# base_module_e1.net
KiCad netlist of a schematic drawn in EAGLE
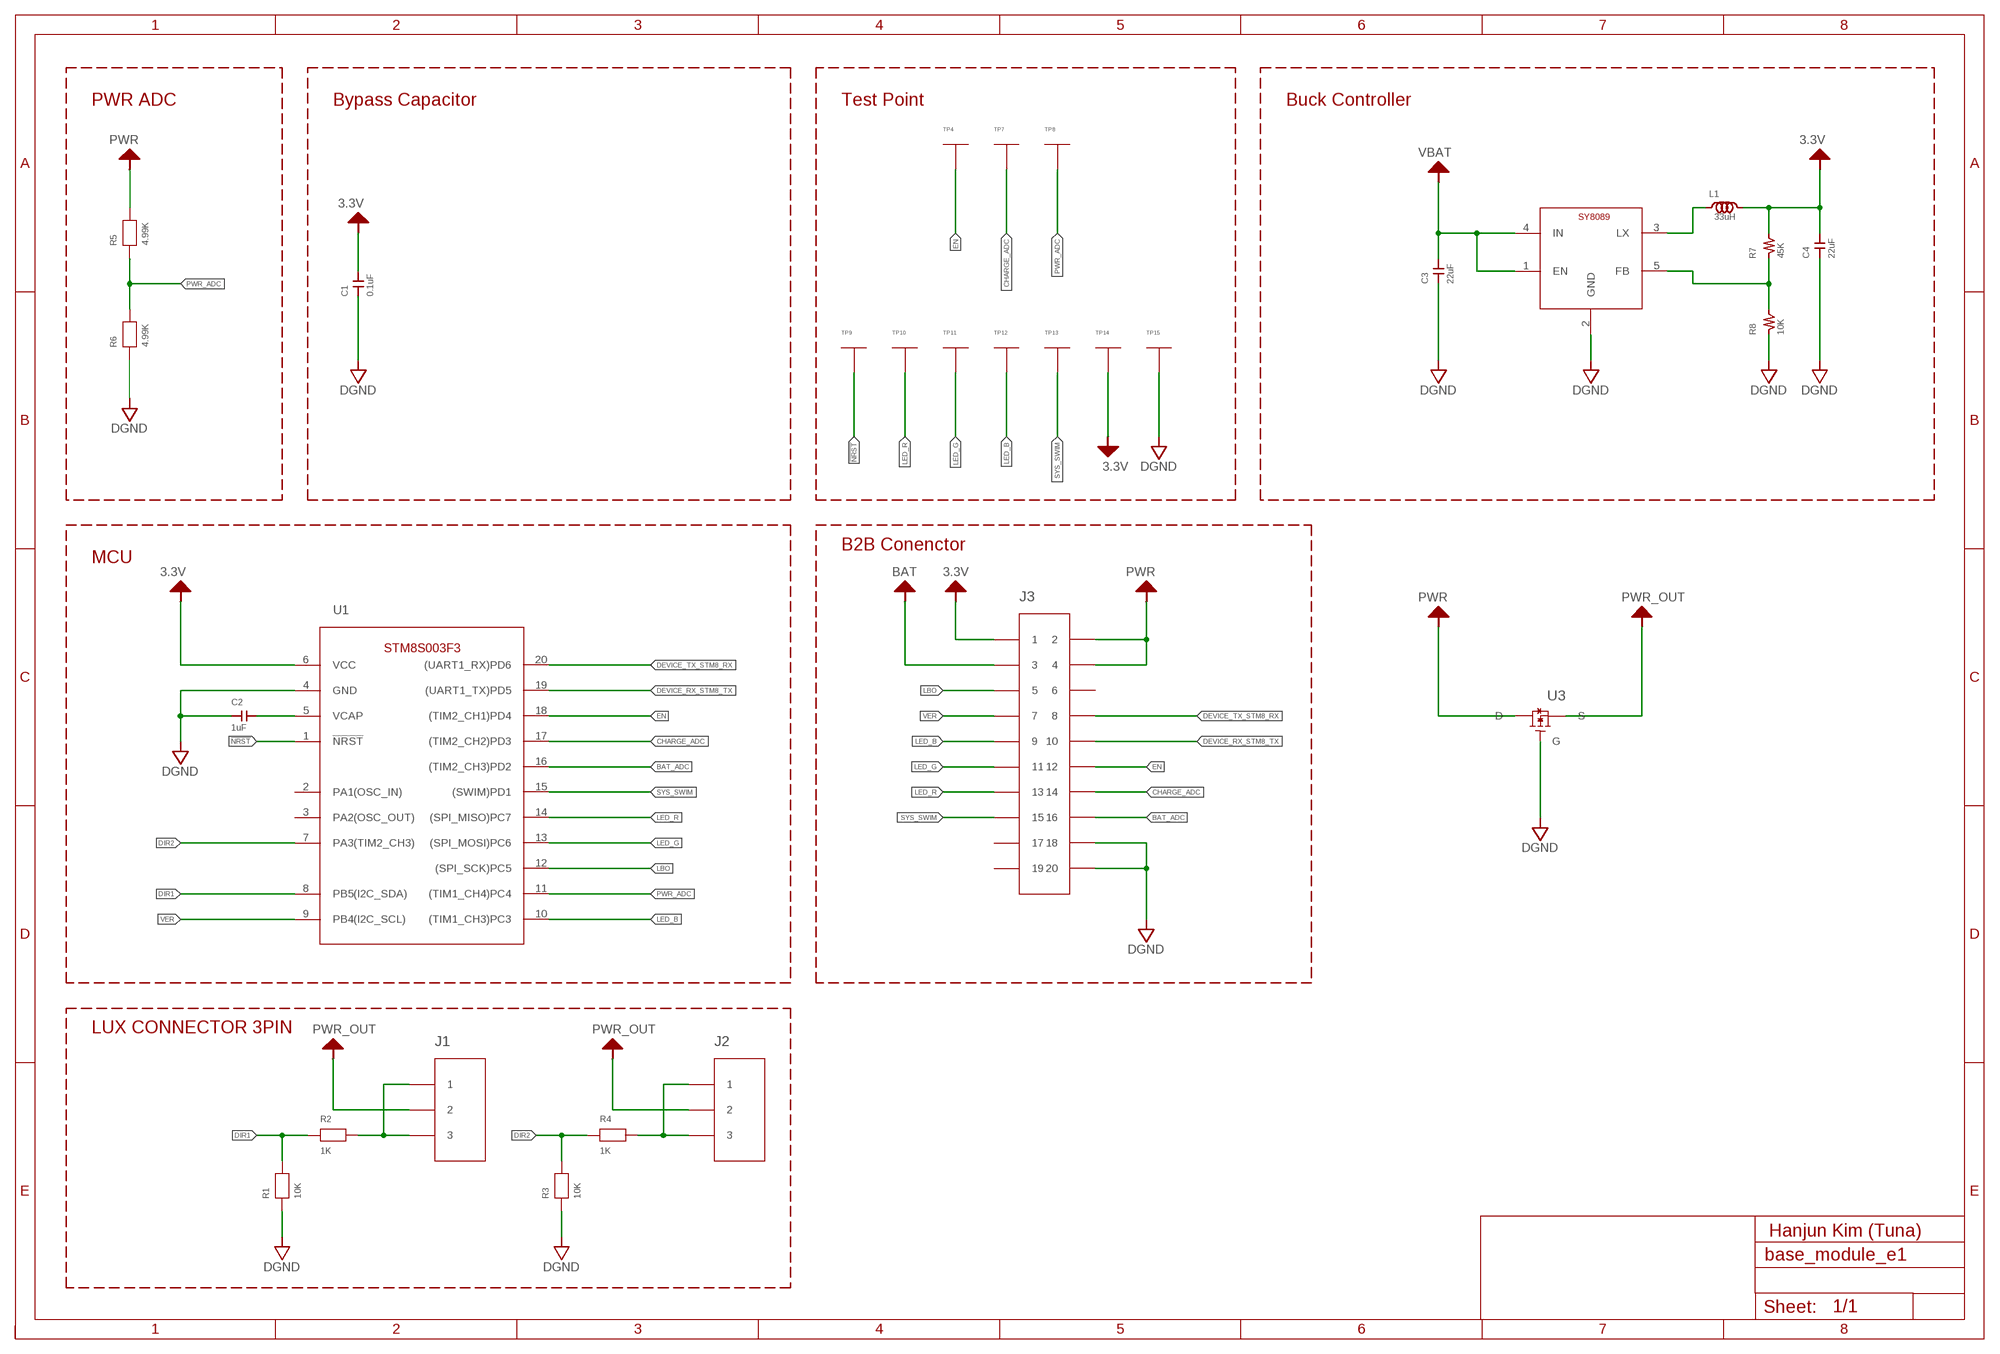
[diagram p0: schematic, sheet 1]

(export (version "E")
  (design (tool "Eeschema 10.0.6"))
  (components
    (comp (ref "C1")
      (value "0.1uF")
      (footprint "eagle-import:1005")
      (libsource (lib "eagle-import") (part "CAPACITOR_CHIP1005"))
    )
    (comp (ref "C2")
      (value "1uF")
      (footprint "eagle-import:1005")
      (libsource (lib "eagle-import") (part "CAPACITOR_CHIP1005"))
    )
    (comp (ref "C3")
      (value "22uF")
      (footprint "eagle-import:1608")
      (libsource (lib "eagle-import") (part "CAPACITOR_CHIP1608"))
    )
    (comp (ref "C4")
      (value "22uF")
      (footprint "eagle-import:1608")
      (libsource (lib "eagle-import") (part "CAPACITOR_CHIP1608"))
    )
    (comp (ref "J1")
      (value "MODI_CONNECTOR_BOTTOM")
      (footprint "eagle-import:3P")
      (libsource (lib "eagle-import") (part "MODI_CONNECTOR_BOTTOM"))
    )
    (comp (ref "J2")
      (value "MODI_CONNECTOR_BOTTOM")
      (footprint "eagle-import:3P")
      (libsource (lib "eagle-import") (part "MODI_CONNECTOR_BOTTOM"))
    )
    (comp (ref "J3")
      (value "AXK720447G")
      (footprint "eagle-import:SOCKET_20P")
      (libsource (lib "eagle-import") (part "AXK720447G"))
    )
    (comp (ref "L1")
      (value "33uH")
      (footprint "eagle-import:2518")
      (libsource (lib "eagle-import") (part "INDUCTOR2518"))
    )
    (comp (ref "P1")
      (value "MODI_BAT_BASE")
      (footprint "eagle-import:BAT_BASE")
      (libsource (lib "eagle-import") (part "MODI_BAT_BASE"))
    )
    (comp (ref "R1")
      (value "10K")
      (footprint "eagle-import:1005")
      (libsource (lib "eagle-import") (part "RESISTOR_CHIP_SMALL1005"))
    )
    (comp (ref "R2")
      (value "1K")
      (footprint "eagle-import:1005")
      (libsource (lib "eagle-import") (part "RESISTOR_CHIP_SMALL1005"))
    )
    (comp (ref "R3")
      (value "10K")
      (footprint "eagle-import:1005")
      (libsource (lib "eagle-import") (part "RESISTOR_CHIP_SMALL1005"))
    )
    (comp (ref "R4")
      (value "1K")
      (footprint "eagle-import:1005")
      (libsource (lib "eagle-import") (part "RESISTOR_CHIP_SMALL1005"))
    )
    (comp (ref "R5")
      (value "4.99K")
      (footprint "eagle-import:1005")
      (libsource (lib "eagle-import") (part "RESISTOR_CHIP_SMALL1005"))
    )
    (comp (ref "R6")
      (value "4.99K")
      (footprint "eagle-import:1005")
      (libsource (lib "eagle-import") (part "RESISTOR_CHIP_SMALL1005"))
    )
    (comp (ref "R7")
      (value "45K")
      (footprint "eagle-import:1005")
      (libsource (lib "eagle-import") (part "RESISTOR_CHIP_1005"))
    )
    (comp (ref "R8")
      (value "10K")
      (footprint "eagle-import:1005")
      (libsource (lib "eagle-import") (part "RESISTOR_CHIP_1005"))
    )
    (comp (ref "TP4")
      (value "TEST_POINT_1.2MM_PAD")
      (footprint "eagle-import:1.2MM_PAD")
      (libsource (lib "eagle-import") (part "TEST_POINT_1.2MM_PAD"))
    )
    (comp (ref "TP7")
      (value "TEST_POINT_1.2MM_PAD")
      (footprint "eagle-import:1.2MM_PAD")
      (libsource (lib "eagle-import") (part "TEST_POINT_1.2MM_PAD"))
    )
    (comp (ref "TP8")
      (value "TEST_POINT_1.2MM_PAD")
      (footprint "eagle-import:1.2MM_PAD")
      (libsource (lib "eagle-import") (part "TEST_POINT_1.2MM_PAD"))
    )
    (comp (ref "TP9")
      (value "TEST_POINT_1.2MM_PAD")
      (footprint "eagle-import:1.2MM_PAD")
      (libsource (lib "eagle-import") (part "TEST_POINT_1.2MM_PAD"))
    )
    (comp (ref "TP10")
      (value "TEST_POINT_1.2MM_PAD")
      (footprint "eagle-import:1.2MM_PAD")
      (libsource (lib "eagle-import") (part "TEST_POINT_1.2MM_PAD"))
    )
    (comp (ref "TP11")
      (value "TEST_POINT_1.2MM_PAD")
      (footprint "eagle-import:1.2MM_PAD")
      (libsource (lib "eagle-import") (part "TEST_POINT_1.2MM_PAD"))
    )
    (comp (ref "TP12")
      (value "TEST_POINT_1.2MM_PAD")
      (footprint "eagle-import:1.2MM_PAD")
      (libsource (lib "eagle-import") (part "TEST_POINT_1.2MM_PAD"))
    )
    (comp (ref "TP13")
      (value "TEST_POINT")
      (footprint "eagle-import:0.7MM_HOLE")
      (libsource (lib "eagle-import") (part "TEST_POINT"))
    )
    (comp (ref "TP14")
      (value "TEST_POINT")
      (footprint "eagle-import:0.7MM_HOLE")
      (libsource (lib "eagle-import") (part "TEST_POINT"))
    )
    (comp (ref "TP15")
      (value "TEST_POINT")
      (footprint "eagle-import:0.7MM_HOLE")
      (libsource (lib "eagle-import") (part "TEST_POINT"))
    )
    (comp (ref "U1")
      (value "STM8S003FXU6")
      (footprint "eagle-import:UFQFPN20")
      (libsource (lib "eagle-import") (part "STM8S003FXU6"))
    )
    (comp (ref "U2")
      (value "SY8089")
      (footprint "eagle-import:SOT-23-5")
      (libsource (lib "eagle-import") (part "SY8089"))
    )
    (comp (ref "U3")
      (value "PMXBXXXXPE")
      (footprint "eagle-import:DFN1010D-3")
      (libsource (lib "eagle-import") (part "PMXBXXXXPE"))
    )
  )
  (nets
    (net (code "1") (name "/~{NRST}") (class "Default")
      (node (ref "TP9") (pin "P1") (pinfunction "P$1_P1") (pintype "bidirectional"))
      (node (ref "U1") (pin "1") (pinfunction "~{NRST}_1") (pintype "bidirectional"))
    )
    (net (code "2") (name "3.3V") (class "Default")
      (node (ref "C1") (pin "P$2") (pinfunction "P$2_P$2") (pintype "passive"))
      (node (ref "C4") (pin "P$2") (pinfunction "P$2_P$2") (pintype "passive"))
      (node (ref "J3") (pin "P1") (pinfunction "1_P1") (pintype "bidirectional"))
      (node (ref "L1") (pin "P$2") (pinfunction "P$2_P$2") (pintype "passive"))
      (node (ref "R7") (pin "P$2") (pinfunction "P$2_P$2") (pintype "passive"))
      (node (ref "TP14") (pin "1") (pinfunction "P$1_1") (pintype "bidirectional"))
      (node (ref "U1") (pin "6") (pinfunction "VCC_6") (pintype "power_in"))
    )
    (net (code "3") (name "BAT") (class "Default")
      (node (ref "C3") (pin "P$2") (pinfunction "P$2_P$2") (pintype "passive"))
      (node (ref "J3") (pin "P3") (pinfunction "3_P3") (pintype "bidirectional"))
      (node (ref "U2") (pin "1") (pinfunction "EN_1") (pintype "bidirectional"))
      (node (ref "U2") (pin "4") (pinfunction "IN_4") (pintype "input"))
    )
    (net (code "4") (name "BAT_ADC") (class "Default")
      (node (ref "J3") (pin "P16") (pinfunction "16_P16") (pintype "bidirectional"))
      (node (ref "U1") (pin "16") (pinfunction "(TIM2_CH3)PD2_16") (pintype "bidirectional"))
    )
    (net (code "5") (name "CHARGE_ADC") (class "Default")
      (node (ref "J3") (pin "P14") (pinfunction "14_P14") (pintype "bidirectional"))
      (node (ref "TP7") (pin "P1") (pinfunction "P$1_P1") (pintype "bidirectional"))
      (node (ref "U1") (pin "17") (pinfunction "(TIM2_CH2)PD3_17") (pintype "bidirectional"))
    )
    (net (code "6") (name "DEVICE_RX_STM8_TX") (class "Default")
      (node (ref "J3") (pin "P10") (pinfunction "10_P10") (pintype "bidirectional"))
      (node (ref "U1") (pin "19") (pinfunction "(UART1_TX)PD5_19") (pintype "bidirectional"))
    )
    (net (code "7") (name "DEVICE_TX_STM8_RX") (class "Default")
      (node (ref "J3") (pin "P8") (pinfunction "8_P8") (pintype "bidirectional"))
      (node (ref "U1") (pin "20") (pinfunction "(UART1_RX)PD6_20") (pintype "bidirectional"))
    )
    (net (code "8") (name "DGND") (class "Default")
      (node (ref "C1") (pin "P$1") (pinfunction "P$1_P$1") (pintype "passive"))
      (node (ref "C2") (pin "P$1") (pinfunction "P$1_P$1") (pintype "passive"))
      (node (ref "C3") (pin "P$1") (pinfunction "P$1_P$1") (pintype "passive"))
      (node (ref "C4") (pin "P$1") (pinfunction "P$1_P$1") (pintype "passive"))
      (node (ref "J3") (pin "P18") (pinfunction "18_P18") (pintype "bidirectional"))
      (node (ref "J3") (pin "P20") (pinfunction "20_P20") (pintype "bidirectional"))
      (node (ref "R1") (pin "P$1") (pinfunction "P$1_P$1") (pintype "bidirectional"))
      (node (ref "R3") (pin "P$1") (pinfunction "P$1_P$1") (pintype "bidirectional"))
      (node (ref "R6") (pin "P$1") (pinfunction "P$1_P$1") (pintype "bidirectional"))
      (node (ref "R8") (pin "P$1") (pinfunction "P$1_P$1") (pintype "passive"))
      (node (ref "TP15") (pin "1") (pinfunction "P$1_1") (pintype "bidirectional"))
      (node (ref "U1") (pin "4") (pinfunction "GND_4") (pintype "power_in"))
      (node (ref "U2") (pin "2") (pinfunction "GND_2") (pintype "power_in"))
      (node (ref "U3") (pin "P1") (pinfunction "G_P1") (pintype "bidirectional"))
    )
    (net (code "9") (name "DIR1") (class "Default")
      (node (ref "R1") (pin "P$2") (pinfunction "P$2_P$2") (pintype "bidirectional"))
      (node (ref "R2") (pin "P$1") (pinfunction "P$1_P$1") (pintype "bidirectional"))
      (node (ref "U1") (pin "8") (pinfunction "PB5(I2C_SDA)_8") (pintype "bidirectional"))
    )
    (net (code "10") (name "DIR2") (class "Default")
      (node (ref "R3") (pin "P$2") (pinfunction "P$2_P$2") (pintype "bidirectional"))
      (node (ref "R4") (pin "P$1") (pinfunction "P$1_P$1") (pintype "bidirectional"))
      (node (ref "U1") (pin "7") (pinfunction "PA3(TIM2_CH3)_7") (pintype "bidirectional"))
    )
    (net (code "11") (name "EN") (class "Default")
      (node (ref "J3") (pin "P12") (pinfunction "12_P12") (pintype "bidirectional"))
      (node (ref "TP4") (pin "P1") (pinfunction "P$1_P1") (pintype "bidirectional"))
      (node (ref "U1") (pin "18") (pinfunction "(TIM2_CH1)PD4_18") (pintype "bidirectional"))
    )
    (net (code "12") (name "LBO") (class "Default")
      (node (ref "J3") (pin "P5") (pinfunction "5_P5") (pintype "bidirectional"))
      (node (ref "U1") (pin "12") (pinfunction "(SPI_SCK)PC5_12") (pintype "bidirectional"))
    )
    (net (code "13") (name "LED_B") (class "Default")
      (node (ref "J3") (pin "P9") (pinfunction "9_P9") (pintype "bidirectional"))
      (node (ref "TP12") (pin "P1") (pinfunction "P$1_P1") (pintype "bidirectional"))
      (node (ref "U1") (pin "10") (pinfunction "(TIM1_CH3)PC3_10") (pintype "bidirectional"))
    )
    (net (code "14") (name "LED_G") (class "Default")
      (node (ref "J3") (pin "P11") (pinfunction "11_P11") (pintype "bidirectional"))
      (node (ref "TP11") (pin "P1") (pinfunction "P$1_P1") (pintype "bidirectional"))
      (node (ref "U1") (pin "13") (pinfunction "(SPI_MOSI)PC6_13") (pintype "bidirectional"))
    )
    (net (code "15") (name "LED_R") (class "Default")
      (node (ref "J3") (pin "P13") (pinfunction "13_P13") (pintype "bidirectional"))
      (node (ref "TP10") (pin "P1") (pinfunction "P$1_P1") (pintype "bidirectional"))
      (node (ref "U1") (pin "14") (pinfunction "(SPI_MISO)PC7_14") (pintype "bidirectional"))
    )
    (net (code "16") (name "Net-(J1-1)") (class "Default")
      (node (ref "J1") (pin "P1") (pinfunction "1_P1") (pintype "bidirectional"))
      (node (ref "J1") (pin "P3") (pinfunction "3_P3") (pintype "bidirectional"))
      (node (ref "R2") (pin "P$2") (pinfunction "P$2_P$2") (pintype "bidirectional"))
    )
    (net (code "17") (name "Net-(J2-1)") (class "Default")
      (node (ref "J2") (pin "P1") (pinfunction "1_P1") (pintype "bidirectional"))
      (node (ref "J2") (pin "P3") (pinfunction "3_P3") (pintype "bidirectional"))
      (node (ref "R4") (pin "P$2") (pinfunction "P$2_P$2") (pintype "bidirectional"))
    )
    (net (code "18") (name "Net-(U1-VCAP)") (class "Default")
      (node (ref "C2") (pin "P$2") (pinfunction "P$2_P$2") (pintype "passive"))
      (node (ref "U1") (pin "5") (pinfunction "VCAP_5") (pintype "power_in"))
    )
    (net (code "19") (name "Net-(U2-FB)") (class "Default")
      (node (ref "R7") (pin "P$1") (pinfunction "P$1_P$1") (pintype "passive"))
      (node (ref "R8") (pin "P$2") (pinfunction "P$2_P$2") (pintype "passive"))
      (node (ref "U2") (pin "5") (pinfunction "FB_5") (pintype "power_in"))
    )
    (net (code "20") (name "Net-(U2-LX)") (class "Default")
      (node (ref "L1") (pin "P$1") (pinfunction "P$1_P$1") (pintype "passive"))
      (node (ref "U2") (pin "3") (pinfunction "LX_3") (pintype "bidirectional"))
    )
    (net (code "21") (name "PWR") (class "Default")
      (node (ref "J3") (pin "P2") (pinfunction "2_P2") (pintype "bidirectional"))
      (node (ref "J3") (pin "P4") (pinfunction "4_P4") (pintype "bidirectional"))
      (node (ref "R5") (pin "P$2") (pinfunction "P$2_P$2") (pintype "bidirectional"))
      (node (ref "U3") (pin "P3") (pinfunction "D_P3") (pintype "bidirectional"))
    )
    (net (code "22") (name "PWR_ADC") (class "Default")
      (node (ref "R5") (pin "P$1") (pinfunction "P$1_P$1") (pintype "bidirectional"))
      (node (ref "R6") (pin "P$2") (pinfunction "P$2_P$2") (pintype "bidirectional"))
      (node (ref "TP8") (pin "P1") (pinfunction "P$1_P1") (pintype "bidirectional"))
      (node (ref "U1") (pin "11") (pinfunction "(TIM1_CH4)PC4_11") (pintype "bidirectional"))
    )
    (net (code "23") (name "PWR_OUT") (class "Default")
      (node (ref "J1") (pin "P2") (pinfunction "2_P2") (pintype "bidirectional"))
      (node (ref "J2") (pin "P2") (pinfunction "2_P2") (pintype "bidirectional"))
      (node (ref "U3") (pin "P2") (pinfunction "S_P2") (pintype "bidirectional"))
    )
    (net (code "24") (name "SYS_SWIM") (class "Default")
      (node (ref "J3") (pin "P15") (pinfunction "15_P15") (pintype "bidirectional"))
      (node (ref "TP13") (pin "1") (pinfunction "P$1_1") (pintype "bidirectional"))
      (node (ref "U1") (pin "15") (pinfunction "(SWIM)PD1_15") (pintype "bidirectional"))
    )
    (net (code "25") (name "VER") (class "Default")
      (node (ref "J3") (pin "P7") (pinfunction "7_P7") (pintype "bidirectional"))
      (node (ref "U1") (pin "9") (pinfunction "PB4(I2C_SCL)_9") (pintype "bidirectional"))
    )
    (net (code "26") (name "unconnected-(J3-6-PadP6)") (class "Default")
      (node (ref "J3") (pin "P6") (pinfunction "6_P6") (pintype "bidirectional"))
    )
    (net (code "27") (name "unconnected-(J3-17-PadP17)") (class "Default")
      (node (ref "J3") (pin "P17") (pinfunction "17_P17") (pintype "bidirectional"))
    )
    (net (code "28") (name "unconnected-(J3-19-PadP19)") (class "Default")
      (node (ref "J3") (pin "P19") (pinfunction "19_P19") (pintype "bidirectional"))
    )
    (net (code "29") (name "unconnected-(U1-PA1(OSC_IN)-Pad2)") (class "Default")
      (node (ref "U1") (pin "2") (pinfunction "PA1(OSC_IN)_2") (pintype "bidirectional"))
    )
    (net (code "30") (name "unconnected-(U1-PA2(OSC_OUT)-Pad3)") (class "Default")
      (node (ref "U1") (pin "3") (pinfunction "PA2(OSC_OUT)_3") (pintype "bidirectional"))
    )
  )
)
